# 0D1__L293D.net
KiCad netlist of a schematic drawn in Altium Designer
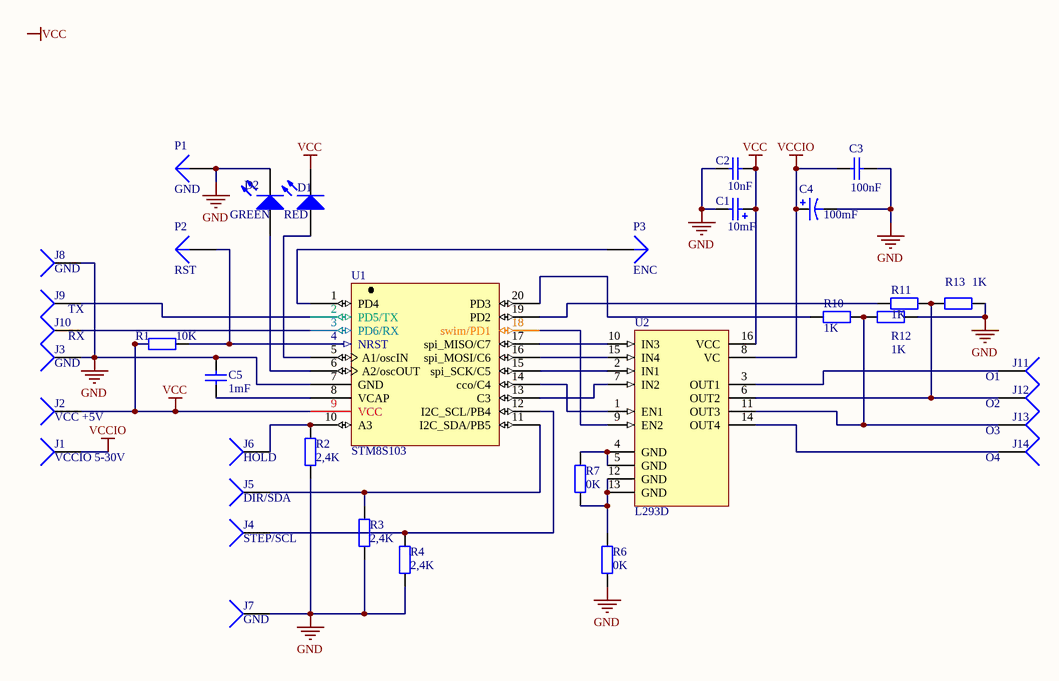
[diagram p0: 0D1_(L293D).SchDoc]

(export (version "E")
  (design (tool "Eeschema 10.0.6"))
  (components
    (comp (ref "C1")
      (value "10mF")
      (footprint "0805")
      (description "Polarized Capacitor (Axial)")
      (fields (field (name "PUBLISHER") "Altium Limited"))
      (libsource (lib "Miscellaneous Devices") (part "Cap Pol2"))
    )
    (comp (ref "C2")
      (value "10nF")
      (footprint "0805")
      (description "Capacitor")
      (fields (field (name "Comment") "Cap") (field (name "PUBLISHER") "Altium Limited"))
      (libsource (lib "Miscellaneous Devices") (part "Cap"))
    )
    (comp (ref "C3")
      (value "100nF")
      (footprint "0805")
      (description "Capacitor")
      (fields (field (name "Comment") "Cap") (field (name "PUBLISHER") "Altium Limited"))
      (libsource (lib "Miscellaneous Devices") (part "Cap"))
    )
    (comp (ref "C4")
      (value "100mF")
      (footprint "RB5-10.5")
      (description "Polarized Capacitor (Radial)")
      (fields (field (name "Comment") "Cap Pol1") (field (name "PUBLISHER") "Altium Limited"))
      (libsource (lib "Miscellaneous Devices") (part "Cap Pol1"))
    )
    (comp (ref "C5")
      (value "1mF")
      (footprint "0805")
      (description "Capacitor")
      (fields (field (name "Comment") "Cap") (field (name "PUBLISHER") "Altium Limited"))
      (libsource (lib "Miscellaneous Devices") (part "Cap"))
    )
    (comp (ref "D1")
      (value "RED")
      (footprint "3.5X2.8X1.9")
      (description "Typical BLUE SiC LED")
      (fields (field (name "PUBLISHER") "Altium Limited"))
      (libsource (lib "Miscellaneous Devices") (part "LED3"))
    )
    (comp (ref "D2")
      (value "GREEN")
      (footprint "3.5X2.8X1.9")
      (description "Typical BLUE SiC LED")
      (fields (field (name "PUBLISHER") "Altium Limited"))
      (libsource (lib "Miscellaneous Devices") (part "LED3"))
    )
    (comp (ref "J1")
      (value "VCCIO 5-30V")
      (footprint "PIN1")
      (description "Socket")
      (fields (field (name "PUBLISHER") "Altium Limited"))
      (libsource (lib "Miscellaneous Connectors") (part "Socket"))
    )
    (comp (ref "J2")
      (value "VCC +5V")
      (footprint "PIN1")
      (description "Socket")
      (fields (field (name "PUBLISHER") "Altium Limited"))
      (libsource (lib "Miscellaneous Connectors") (part "Socket"))
    )
    (comp (ref "J3")
      (value "GND")
      (footprint "PIN1")
      (description "Socket")
      (fields (field (name "PUBLISHER") "Altium Limited"))
      (libsource (lib "Miscellaneous Connectors") (part "Socket"))
    )
    (comp (ref "J4")
      (value "STEP/SCL")
      (footprint "PIN1")
      (description "Socket")
      (fields (field (name "PUBLISHER") "Altium Limited"))
      (libsource (lib "Miscellaneous Connectors") (part "Socket"))
    )
    (comp (ref "J5")
      (value "DIR/SDA")
      (footprint "PIN1")
      (description "Socket")
      (fields (field (name "PUBLISHER") "Altium Limited"))
      (libsource (lib "Miscellaneous Connectors") (part "Socket"))
    )
    (comp (ref "J6")
      (value "HOLD")
      (footprint "PIN1")
      (description "Socket")
      (fields (field (name "PUBLISHER") "Altium Limited"))
      (libsource (lib "Miscellaneous Connectors") (part "Socket"))
    )
    (comp (ref "J7")
      (value "GND")
      (footprint "PIN1")
      (description "Socket")
      (fields (field (name "PUBLISHER") "Altium Limited"))
      (libsource (lib "Miscellaneous Connectors") (part "Socket"))
    )
    (comp (ref "J8")
      (value "GND")
      (footprint "PIN1")
      (description "Socket")
      (fields (field (name "PUBLISHER") "Altium Limited"))
      (libsource (lib "Miscellaneous Connectors") (part "Socket"))
    )
    (comp (ref "J9")
      (value "TX")
      (footprint "PIN1")
      (description "Socket")
      (fields (field (name "PUBLISHER") "Altium Limited"))
      (libsource (lib "Miscellaneous Connectors") (part "Socket"))
    )
    (comp (ref "J10")
      (value "RX")
      (footprint "PIN1")
      (description "Socket")
      (fields (field (name "PUBLISHER") "Altium Limited"))
      (libsource (lib "Miscellaneous Connectors") (part "Socket"))
    )
    (comp (ref "J11")
      (value "O1")
      (footprint "PIN1")
      (description "Socket")
      (fields (field (name "PUBLISHER") "Altium Limited"))
      (libsource (lib "Miscellaneous Connectors") (part "Socket"))
    )
    (comp (ref "J12")
      (value "O2")
      (footprint "PIN1")
      (description "Socket")
      (fields (field (name "PUBLISHER") "Altium Limited"))
      (libsource (lib "Miscellaneous Connectors") (part "Socket"))
    )
    (comp (ref "J13")
      (value "O3")
      (footprint "PIN1")
      (description "Socket")
      (fields (field (name "PUBLISHER") "Altium Limited"))
      (libsource (lib "Miscellaneous Connectors") (part "Socket"))
    )
    (comp (ref "J14")
      (value "O4")
      (footprint "PIN1")
      (description "Socket")
      (fields (field (name "PUBLISHER") "Altium Limited"))
      (libsource (lib "Miscellaneous Connectors") (part "Socket"))
    )
    (comp (ref "P1")
      (value "GND")
      (footprint "PIN1")
      (description "Plug")
      (fields (field (name "PUBLISHER") "Altium Limited"))
      (libsource (lib "Miscellaneous Connectors") (part "Plug"))
    )
    (comp (ref "P2")
      (value "RST")
      (footprint "PIN1")
      (description "Plug")
      (fields (field (name "PUBLISHER") "Altium Limited"))
      (libsource (lib "Miscellaneous Connectors") (part "Plug"))
    )
    (comp (ref "P3")
      (value "ENC")
      (footprint "PIN1")
      (description "Plug")
      (fields (field (name "PUBLISHER") "Altium Limited"))
      (libsource (lib "Miscellaneous Connectors") (part "Plug"))
    )
    (comp (ref "R1")
      (value "10K")
      (footprint "0805")
      (description "Resistor")
      (fields (field (name "Comment") "Res2") (field (name "PUBLISHER") "Altium Limited"))
      (libsource (lib "") (part "Res2_2"))
    )
    (comp (ref "R2")
      (value "2,4K")
      (footprint "0805")
      (description "Resistor")
      (fields (field (name "Comment") "Res2") (field (name "PUBLISHER") "Altium Limited"))
      (libsource (lib "Miscellaneous Devices") (part "Res2"))
    )
    (comp (ref "R3")
      (value "2,4K")
      (footprint "0805")
      (description "Resistor")
      (fields (field (name "Comment") "Res2") (field (name "PUBLISHER") "Altium Limited"))
      (libsource (lib "Miscellaneous Devices") (part "Res2"))
    )
    (comp (ref "R4")
      (value "2,4K")
      (footprint "0805")
      (description "Resistor")
      (fields (field (name "Comment") "Res2") (field (name "PUBLISHER") "Altium Limited"))
      (libsource (lib "Miscellaneous Devices") (part "Res2"))
    )
    (comp (ref "R6")
      (value "0K")
      (footprint "1206")
      (description "Resistor")
      (fields (field (name "Comment") "Res2") (field (name "PUBLISHER") "Altium Limited"))
      (libsource (lib "Miscellaneous Devices") (part "Res2"))
    )
    (comp (ref "R7")
      (value "0K")
      (footprint "1812")
      (description "Resistor")
      (fields (field (name "Comment") "Res2") (field (name "PUBLISHER") "Altium Limited"))
      (libsource (lib "Miscellaneous Devices") (part "Res2"))
    )
    (comp (ref "R10")
      (value "1K")
      (footprint "RESC0805(2012)_M")
      (description "Resistor")
      (fields (field (name "Comment") "Res2") (field (name "PUBLISHER") "Altium Limited"))
      (libsource (lib "") (part "Res2_2"))
    )
    (comp (ref "R11")
      (value "1K")
      (footprint "RESC0805(2012)_M")
      (description "Resistor")
      (fields (field (name "Comment") "Res2") (field (name "PUBLISHER") "Altium Limited"))
      (libsource (lib "") (part "Res2_2"))
    )
    (comp (ref "R12")
      (value "1K")
      (footprint "RESC0805(2012)_M")
      (description "Resistor")
      (fields (field (name "Comment") "Res2") (field (name "PUBLISHER") "Altium Limited"))
      (libsource (lib "") (part "Res2_1"))
    )
    (comp (ref "R13")
      (value "1K")
      (footprint "RESC0805(2012)_M")
      (description "Resistor")
      (fields (field (name "Comment") "Res2") (field (name "PUBLISHER") "Altium Limited"))
      (libsource (lib "") (part "Res2_1"))
    )
    (comp (ref "U1") (value "STM8S103") (footprint "TSSOP20") (libsource (lib "STM8S") (part "STM8S103")))
    (comp (ref "U2")
      (value "L293D")
      (footprint "DIP16")
      (description "Push-Pull Four Channel Driver With Diode")
      (fields (field (name "PUBLISHER") "Altium Limited"))
      (libsource (lib "ST Interface DC & Stepper Motor Controller") (part "L293D"))
    )
  )
  (nets
    (net (code "1") (name "GND") (class "Default")
      (node (ref "C1") (pin "2") (pinfunction "2_2") (pintype "passive"))
      (node (ref "C2") (pin "2") (pinfunction "2_2") (pintype "passive"))
      (node (ref "C3") (pin "2") (pinfunction "2_2") (pintype "passive"))
      (node (ref "C4") (pin "2") (pinfunction "2_2") (pintype "passive"))
      (node (ref "C5") (pin "1") (pinfunction "1_1") (pintype "passive"))
      (node (ref "D2") (pin "2") (pinfunction "K_2") (pintype "passive"))
      (node (ref "J3") (pin "1") (pinfunction "1_1") (pintype "passive"))
      (node (ref "J7") (pin "1") (pinfunction "1_1") (pintype "passive"))
      (node (ref "J8") (pin "1") (pinfunction "1_1") (pintype "passive"))
      (node (ref "P1") (pin "1") (pinfunction "1_1") (pintype "passive"))
      (node (ref "R12") (pin "2") (pinfunction "2_2") (pintype "passive"))
      (node (ref "R13") (pin "2") (pinfunction "2_2") (pintype "passive"))
      (node (ref "R2") (pin "2") (pinfunction "2_2") (pintype "passive"))
      (node (ref "R3") (pin "2") (pinfunction "2_2") (pintype "passive"))
      (node (ref "R4") (pin "2") (pinfunction "2_2") (pintype "passive"))
      (node (ref "R6") (pin "2") (pinfunction "2_2") (pintype "passive"))
      (node (ref "U1") (pin "7") (pinfunction "GND_7") (pintype "power_in"))
    )
    (net (code "2") (name "Net-(D1-A)") (class "Default")
      (node (ref "D1") (pin "1") (pinfunction "A_1") (pintype "passive"))
      (node (ref "U1") (pin "5") (pinfunction "A1/oscIN_5") (pintype "bidirectional"))
    )
    (net (code "3") (name "Net-(D2-A)") (class "Default")
      (node (ref "D2") (pin "1") (pinfunction "A_1") (pintype "passive"))
      (node (ref "U1") (pin "6") (pinfunction "A2/oscOUT_6") (pintype "bidirectional"))
    )
    (net (code "4") (name "Net-(R6-Pad1)") (class "Default")
      (node (ref "R6") (pin "1") (pinfunction "1_1") (pintype "passive"))
      (node (ref "R7") (pin "2") (pinfunction "2_2") (pintype "passive"))
      (node (ref "U2") (pin "12") (pinfunction "GND_12") (pintype "power_in"))
      (node (ref "U2") (pin "13") (pinfunction "GND_13") (pintype "power_in"))
    )
    (net (code "5") (name "Net-(R7-Pad1)") (class "Default")
      (node (ref "R7") (pin "1") (pinfunction "1_1") (pintype "passive"))
      (node (ref "U2") (pin "4") (pinfunction "GND_4") (pintype "power_in"))
      (node (ref "U2") (pin "5") (pinfunction "GND_5") (pintype "power_in"))
    )
    (net (code "6") (name "Net-(U1-A3)") (class "Default")
      (node (ref "J6") (pin "1") (pinfunction "1_1") (pintype "passive"))
      (node (ref "R2") (pin "1") (pinfunction "1_1") (pintype "passive"))
      (node (ref "U1") (pin "10") (pinfunction "A3_10") (pintype "bidirectional"))
    )
    (net (code "7") (name "Net-(U1-C3)") (class "Default")
      (node (ref "U1") (pin "13") (pinfunction "C3_13") (pintype "bidirectional"))
      (node (ref "U2") (pin "7") (pinfunction "IN2_7") (pintype "input"))
    )
    (net (code "8") (name "Net-(U1-I2C_SCL{slash}PB4)") (class "Default")
      (node (ref "J4") (pin "1") (pinfunction "1_1") (pintype "passive"))
      (node (ref "R4") (pin "1") (pinfunction "1_1") (pintype "passive"))
      (node (ref "U1") (pin "12") (pinfunction "I2C_SCL/PB4_12") (pintype "bidirectional"))
    )
    (net (code "9") (name "Net-(U1-I2C_SDA{slash}PB5)") (class "Default")
      (node (ref "J5") (pin "1") (pinfunction "1_1") (pintype "passive"))
      (node (ref "R3") (pin "1") (pinfunction "1_1") (pintype "passive"))
      (node (ref "U1") (pin "11") (pinfunction "I2C_SDA/PB5_11") (pintype "bidirectional"))
    )
    (net (code "10") (name "Net-(U1-NRST)") (class "Default")
      (node (ref "P2") (pin "1") (pinfunction "1_1") (pintype "passive"))
      (node (ref "R1") (pin "1") (pinfunction "1_1") (pintype "passive"))
      (node (ref "U1") (pin "4") (pinfunction "NRST_4") (pintype "input"))
    )
    (net (code "11") (name "Net-(U1-PD2)") (class "Default")
      (node (ref "R11") (pin "2") (pinfunction "2_2") (pintype "passive"))
      (node (ref "U1") (pin "19") (pinfunction "PD2_19") (pintype "bidirectional"))
    )
    (net (code "12") (name "Net-(U1-PD3)") (class "Default")
      (node (ref "R10") (pin "2") (pinfunction "2_2") (pintype "passive"))
      (node (ref "U1") (pin "20") (pinfunction "PD3_20") (pintype "bidirectional"))
    )
    (net (code "13") (name "Net-(U1-PD4)") (class "Default")
      (node (ref "P3") (pin "1") (pinfunction "1_1") (pintype "passive"))
      (node (ref "U1") (pin "1") (pinfunction "PD4_1") (pintype "bidirectional"))
    )
    (net (code "14") (name "Net-(U1-PD5{slash}TX)") (class "Default")
      (node (ref "J9") (pin "1") (pinfunction "1_1") (pintype "passive"))
      (node (ref "U1") (pin "2") (pinfunction "PD5/TX_2") (pintype "bidirectional"))
    )
    (net (code "15") (name "Net-(U1-PD6{slash}RX)") (class "Default")
      (node (ref "J10") (pin "1") (pinfunction "1_1") (pintype "passive"))
      (node (ref "U1") (pin "3") (pinfunction "PD6/RX_3") (pintype "bidirectional"))
    )
    (net (code "16") (name "Net-(U1-VCAP)") (class "Default")
      (node (ref "C5") (pin "2") (pinfunction "2_2") (pintype "passive"))
      (node (ref "U1") (pin "8") (pinfunction "VCAP_8") (pintype "power_in"))
    )
    (net (code "17") (name "Net-(U1-cco{slash}C4)") (class "Default")
      (node (ref "U1") (pin "14") (pinfunction "cco/C4_14") (pintype "bidirectional"))
      (node (ref "U2") (pin "1") (pinfunction "EN1_1") (pintype "input"))
    )
    (net (code "18") (name "Net-(U1-spi_MISO{slash}C7)") (class "Default")
      (node (ref "U1") (pin "17") (pinfunction "spi_MISO/C7_17") (pintype "bidirectional"))
      (node (ref "U2") (pin "10") (pinfunction "IN3_10") (pintype "input"))
    )
    (net (code "19") (name "Net-(U1-spi_MOSI{slash}C6)") (class "Default")
      (node (ref "U1") (pin "16") (pinfunction "spi_MOSI/C6_16") (pintype "bidirectional"))
      (node (ref "U2") (pin "15") (pinfunction "IN4_15") (pintype "input"))
    )
    (net (code "20") (name "Net-(U1-spi_SCK{slash}C5)") (class "Default")
      (node (ref "U1") (pin "15") (pinfunction "spi_SCK/C5_15") (pintype "bidirectional"))
      (node (ref "U2") (pin "2") (pinfunction "IN1_2") (pintype "input"))
    )
    (net (code "21") (name "Net-(U1-swim{slash}PD1)") (class "Default")
      (node (ref "U1") (pin "18") (pinfunction "swim/PD1_18") (pintype "bidirectional"))
      (node (ref "U2") (pin "9") (pinfunction "EN2_9") (pintype "input"))
    )
    (net (code "22") (name "Net-(U2-OUT1)") (class "Default")
      (node (ref "J11") (pin "1") (pinfunction "1_1") (pintype "passive"))
      (node (ref "U2") (pin "3") (pinfunction "OUT1_3") (pintype "tri_state"))
    )
    (net (code "23") (name "Net-(U2-OUT2)") (class "Default")
      (node (ref "J12") (pin "1") (pinfunction "1_1") (pintype "passive"))
      (node (ref "R11") (pin "1") (pinfunction "1_1") (pintype "passive"))
      (node (ref "R13") (pin "1") (pinfunction "1_1") (pintype "passive"))
      (node (ref "U2") (pin "6") (pinfunction "OUT2_6") (pintype "tri_state"))
    )
    (net (code "24") (name "Net-(U2-OUT3)") (class "Default")
      (node (ref "J13") (pin "1") (pinfunction "1_1") (pintype "passive"))
      (node (ref "R10") (pin "1") (pinfunction "1_1") (pintype "passive"))
      (node (ref "R12") (pin "1") (pinfunction "1_1") (pintype "passive"))
      (node (ref "U2") (pin "11") (pinfunction "OUT3_11") (pintype "tri_state"))
    )
    (net (code "25") (name "Net-(U2-OUT4)") (class "Default")
      (node (ref "J14") (pin "1") (pinfunction "1_1") (pintype "passive"))
      (node (ref "U2") (pin "14") (pinfunction "OUT4_14") (pintype "tri_state"))
    )
    (net (code "26") (name "VCC") (class "Default")
      (node (ref "C1") (pin "1") (pinfunction "1_1") (pintype "passive"))
      (node (ref "C2") (pin "1") (pinfunction "1_1") (pintype "passive"))
      (node (ref "D1") (pin "2") (pinfunction "K_2") (pintype "passive"))
      (node (ref "J2") (pin "1") (pinfunction "1_1") (pintype "passive"))
      (node (ref "R1") (pin "2") (pinfunction "2_2") (pintype "passive"))
      (node (ref "U1") (pin "9") (pinfunction "VCC_9") (pintype "power_in"))
      (node (ref "U2") (pin "16") (pinfunction "VCC_16") (pintype "power_in"))
    )
    (net (code "27") (name "VCCIO") (class "Default")
      (node (ref "C3") (pin "1") (pinfunction "1_1") (pintype "passive"))
      (node (ref "C4") (pin "1") (pinfunction "1_1") (pintype "passive"))
      (node (ref "J1") (pin "1") (pinfunction "1_1") (pintype "passive"))
      (node (ref "U2") (pin "8") (pinfunction "VC_8") (pintype "power_in"))
    )
  )
)
